# control_panel2.net
KiCad netlist of a schematic drawn in EAGLE
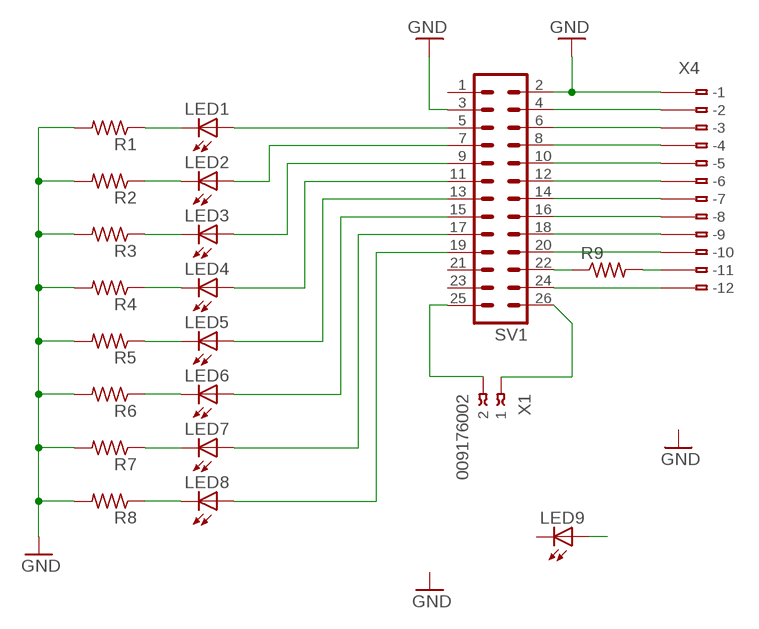
[diagram p0: schematic, sheet 1]

(export (version "E")
  (design (tool "Eeschema 10.0.6"))
  (components
    (comp (ref "LED1")
      (value "LED3MM")
      (footprint "eagle-import:LED3MM")
      (libsource (lib "eagle-import") (part "LED3MM"))
    )
    (comp (ref "LED2")
      (value "LED3MM")
      (footprint "eagle-import:LED3MM")
      (libsource (lib "eagle-import") (part "LED3MM"))
    )
    (comp (ref "LED3")
      (value "LED3MM")
      (footprint "eagle-import:LED3MM")
      (libsource (lib "eagle-import") (part "LED3MM"))
    )
    (comp (ref "LED4")
      (value "LED3MM")
      (footprint "eagle-import:LED3MM")
      (libsource (lib "eagle-import") (part "LED3MM"))
    )
    (comp (ref "LED5")
      (value "LED3MM")
      (footprint "eagle-import:LED3MM")
      (libsource (lib "eagle-import") (part "LED3MM"))
    )
    (comp (ref "LED6")
      (value "LED3MM")
      (footprint "eagle-import:LED3MM")
      (libsource (lib "eagle-import") (part "LED3MM"))
    )
    (comp (ref "LED7")
      (value "LED3MM")
      (footprint "eagle-import:LED3MM")
      (libsource (lib "eagle-import") (part "LED3MM"))
    )
    (comp (ref "LED8")
      (value "LED3MM")
      (footprint "eagle-import:LED3MM")
      (libsource (lib "eagle-import") (part "LED3MM"))
    )
    (comp (ref "LED9")
      (value "LED3MM")
      (footprint "eagle-import:LED3MM")
      (libsource (lib "eagle-import") (part "LED3MM"))
    )
    (comp (ref "R1")
      (value "R-US_0309/V")
      (footprint "eagle-import:0309V")
      (libsource (lib "eagle-import") (part "R-US_0309/V"))
    )
    (comp (ref "R2")
      (value "R-US_0309/V")
      (footprint "eagle-import:0309V")
      (libsource (lib "eagle-import") (part "R-US_0309/V"))
    )
    (comp (ref "R3")
      (value "R-US_0309/V")
      (footprint "eagle-import:0309V")
      (libsource (lib "eagle-import") (part "R-US_0309/V"))
    )
    (comp (ref "R4")
      (value "R-US_0309/V")
      (footprint "eagle-import:0309V")
      (libsource (lib "eagle-import") (part "R-US_0309/V"))
    )
    (comp (ref "R5")
      (value "R-US_0309/V")
      (footprint "eagle-import:0309V")
      (libsource (lib "eagle-import") (part "R-US_0309/V"))
    )
    (comp (ref "R6")
      (value "R-US_0309/V")
      (footprint "eagle-import:0309V")
      (libsource (lib "eagle-import") (part "R-US_0309/V"))
    )
    (comp (ref "R7")
      (value "R-US_0309/V")
      (footprint "eagle-import:0309V")
      (libsource (lib "eagle-import") (part "R-US_0309/V"))
    )
    (comp (ref "R8")
      (value "R-US_0309/V")
      (footprint "eagle-import:0309V")
      (libsource (lib "eagle-import") (part "R-US_0309/V"))
    )
    (comp (ref "R9")
      (value "R-US_0204/7")
      (footprint "eagle-import:0204_7")
      (libsource (lib "eagle-import") (part "R-US_0204/7"))
    )
    (comp (ref "SV1")
      (value "MA13-2")
      (footprint "eagle-import:MA13-2")
      (libsource (lib "eagle-import") (part "MA13-2"))
    )
    (comp (ref "X1")
      (value "009176002")
      (footprint "eagle-import:009176002")
      (fields (field (name "MPN") "009176002001006"))
      (libsource (lib "eagle-import") (part "00917?0026"))
    )
    (comp (ref "X4")
      (value "233-212")
      (footprint "eagle-import:233-212")
      (libsource (lib "eagle-import") (part "233-212"))
    )
  )
  (nets
    (net (code "1") (name "GND") (class "Default")
      (node (ref "R1") (pin "2") (pinfunction "2_2") (pintype "passive"))
      (node (ref "R2") (pin "2") (pinfunction "2_2") (pintype "passive"))
      (node (ref "R3") (pin "2") (pinfunction "2_2") (pintype "passive"))
      (node (ref "R4") (pin "2") (pinfunction "2_2") (pintype "passive"))
      (node (ref "R5") (pin "2") (pinfunction "2_2") (pintype "passive"))
      (node (ref "R6") (pin "2") (pinfunction "2_2") (pintype "passive"))
      (node (ref "R7") (pin "2") (pinfunction "2_2") (pintype "passive"))
      (node (ref "R8") (pin "2") (pinfunction "2_2") (pintype "passive"))
      (node (ref "SV1") (pin "2") (pinfunction "2_2") (pintype "passive"))
      (node (ref "SV1") (pin "3") (pinfunction "3_3") (pintype "passive"))
      (node (ref "X4") (pin "B1") (pinfunction "B-1_B1") (pintype "passive"))
    )
    (net (code "2") (name "Net-(LED1-C)") (class "Default")
      (node (ref "LED1") (pin "K") (pinfunction "C_K") (pintype "passive"))
      (node (ref "R1") (pin "1") (pinfunction "1_1") (pintype "passive"))
    )
    (net (code "3") (name "Net-(LED1-PadA)") (class "Default")
      (node (ref "LED1") (pin "A") (pinfunction "A_A") (pintype "passive"))
      (node (ref "SV1") (pin "5") (pinfunction "5_5") (pintype "passive"))
    )
    (net (code "4") (name "Net-(LED2-C)") (class "Default")
      (node (ref "LED2") (pin "K") (pinfunction "C_K") (pintype "passive"))
      (node (ref "R2") (pin "1") (pinfunction "1_1") (pintype "passive"))
    )
    (net (code "5") (name "Net-(LED2-PadA)") (class "Default")
      (node (ref "LED2") (pin "A") (pinfunction "A_A") (pintype "passive"))
      (node (ref "SV1") (pin "7") (pinfunction "7_7") (pintype "passive"))
    )
    (net (code "6") (name "Net-(LED3-C)") (class "Default")
      (node (ref "LED3") (pin "K") (pinfunction "C_K") (pintype "passive"))
      (node (ref "R3") (pin "1") (pinfunction "1_1") (pintype "passive"))
    )
    (net (code "7") (name "Net-(LED3-PadA)") (class "Default")
      (node (ref "LED3") (pin "A") (pinfunction "A_A") (pintype "passive"))
      (node (ref "SV1") (pin "9") (pinfunction "9_9") (pintype "passive"))
    )
    (net (code "8") (name "Net-(LED4-C)") (class "Default")
      (node (ref "LED4") (pin "K") (pinfunction "C_K") (pintype "passive"))
      (node (ref "R4") (pin "1") (pinfunction "1_1") (pintype "passive"))
    )
    (net (code "9") (name "Net-(LED4-PadA)") (class "Default")
      (node (ref "LED4") (pin "A") (pinfunction "A_A") (pintype "passive"))
      (node (ref "SV1") (pin "11") (pinfunction "11_11") (pintype "passive"))
    )
    (net (code "10") (name "Net-(LED5-C)") (class "Default")
      (node (ref "LED5") (pin "K") (pinfunction "C_K") (pintype "passive"))
      (node (ref "R5") (pin "1") (pinfunction "1_1") (pintype "passive"))
    )
    (net (code "11") (name "Net-(LED5-PadA)") (class "Default")
      (node (ref "LED5") (pin "A") (pinfunction "A_A") (pintype "passive"))
      (node (ref "SV1") (pin "13") (pinfunction "13_13") (pintype "passive"))
    )
    (net (code "12") (name "Net-(LED6-C)") (class "Default")
      (node (ref "LED6") (pin "K") (pinfunction "C_K") (pintype "passive"))
      (node (ref "R6") (pin "1") (pinfunction "1_1") (pintype "passive"))
    )
    (net (code "13") (name "Net-(LED6-PadA)") (class "Default")
      (node (ref "LED6") (pin "A") (pinfunction "A_A") (pintype "passive"))
      (node (ref "SV1") (pin "15") (pinfunction "15_15") (pintype "passive"))
    )
    (net (code "14") (name "Net-(LED7-C)") (class "Default")
      (node (ref "LED7") (pin "K") (pinfunction "C_K") (pintype "passive"))
      (node (ref "R7") (pin "1") (pinfunction "1_1") (pintype "passive"))
    )
    (net (code "15") (name "Net-(LED7-PadA)") (class "Default")
      (node (ref "LED7") (pin "A") (pinfunction "A_A") (pintype "passive"))
      (node (ref "SV1") (pin "17") (pinfunction "17_17") (pintype "passive"))
    )
    (net (code "16") (name "Net-(LED8-C)") (class "Default")
      (node (ref "LED8") (pin "K") (pinfunction "C_K") (pintype "passive"))
      (node (ref "R8") (pin "1") (pinfunction "1_1") (pintype "passive"))
    )
    (net (code "17") (name "Net-(LED8-PadA)") (class "Default")
      (node (ref "LED8") (pin "A") (pinfunction "A_A") (pintype "passive"))
      (node (ref "SV1") (pin "19") (pinfunction "19_19") (pintype "passive"))
    )
    (net (code "18") (name "Net-(R9-Pad1)") (class "Default")
      (node (ref "R9") (pin "1") (pinfunction "1_1") (pintype "passive"))
      (node (ref "SV1") (pin "22") (pinfunction "22_22") (pintype "passive"))
    )
    (net (code "19") (name "Net-(SV1-Pad25)") (class "Default")
      (node (ref "SV1") (pin "25") (pinfunction "25_25") (pintype "passive"))
      (node (ref "X1") (pin "2") (pinfunction "2_2") (pintype "passive"))
    )
    (net (code "20") (name "Net-(SV1-Pad26)") (class "Default")
      (node (ref "SV1") (pin "26") (pinfunction "26_26") (pintype "passive"))
      (node (ref "X1") (pin "1") (pinfunction "1_1") (pintype "passive"))
    )
    (net (code "21") (name "Net-(X4-B-2)") (class "Default")
      (node (ref "SV1") (pin "4") (pinfunction "4_4") (pintype "passive"))
      (node (ref "X4") (pin "B2") (pinfunction "B-2_B2") (pintype "passive"))
    )
    (net (code "22") (name "Net-(X4-B-3)") (class "Default")
      (node (ref "SV1") (pin "6") (pinfunction "6_6") (pintype "passive"))
      (node (ref "X4") (pin "B3") (pinfunction "B-3_B3") (pintype "passive"))
    )
    (net (code "23") (name "Net-(X4-B-4)") (class "Default")
      (node (ref "SV1") (pin "8") (pinfunction "8_8") (pintype "passive"))
      (node (ref "X4") (pin "B4") (pinfunction "B-4_B4") (pintype "passive"))
    )
    (net (code "24") (name "Net-(X4-B-5)") (class "Default")
      (node (ref "SV1") (pin "10") (pinfunction "10_10") (pintype "passive"))
      (node (ref "X4") (pin "B5") (pinfunction "B-5_B5") (pintype "passive"))
    )
    (net (code "25") (name "Net-(X4-B-6)") (class "Default")
      (node (ref "SV1") (pin "12") (pinfunction "12_12") (pintype "passive"))
      (node (ref "X4") (pin "B6") (pinfunction "B-6_B6") (pintype "passive"))
    )
    (net (code "26") (name "Net-(X4-B-7)") (class "Default")
      (node (ref "SV1") (pin "14") (pinfunction "14_14") (pintype "passive"))
      (node (ref "X4") (pin "B7") (pinfunction "B-7_B7") (pintype "passive"))
    )
    (net (code "27") (name "Net-(X4-B-8)") (class "Default")
      (node (ref "SV1") (pin "16") (pinfunction "16_16") (pintype "passive"))
      (node (ref "X4") (pin "B8") (pinfunction "B-8_B8") (pintype "passive"))
    )
    (net (code "28") (name "Net-(X4-B-9)") (class "Default")
      (node (ref "SV1") (pin "18") (pinfunction "18_18") (pintype "passive"))
      (node (ref "X4") (pin "B9") (pinfunction "B-9_B9") (pintype "passive"))
    )
    (net (code "29") (name "Net-(X4-B-10)") (class "Default")
      (node (ref "SV1") (pin "20") (pinfunction "20_20") (pintype "passive"))
      (node (ref "X4") (pin "B10") (pinfunction "B-10_B10") (pintype "passive"))
    )
    (net (code "30") (name "Net-(X4-B-11)") (class "Default")
      (node (ref "R9") (pin "2") (pinfunction "2_2") (pintype "passive"))
      (node (ref "X4") (pin "B11") (pinfunction "B-11_B11") (pintype "passive"))
    )
    (net (code "31") (name "Net-(X4-B-12)") (class "Default")
      (node (ref "SV1") (pin "24") (pinfunction "24_24") (pintype "passive"))
      (node (ref "X4") (pin "B12") (pinfunction "B-12_B12") (pintype "passive"))
    )
    (net (code "32") (name "unconnected-(LED9-C-PadK)") (class "Default")
      (node (ref "LED9") (pin "K") (pinfunction "C_K") (pintype "passive"))
    )
    (net (code "33") (name "unconnected-(LED9-PadA)") (class "Default")
      (node (ref "LED9") (pin "A") (pinfunction "A_A") (pintype "passive"))
    )
    (net (code "34") (name "unconnected-(SV1-Pad1)") (class "Default")
      (node (ref "SV1") (pin "1") (pinfunction "1_1") (pintype "passive"))
    )
    (net (code "35") (name "unconnected-(SV1-Pad21)") (class "Default")
      (node (ref "SV1") (pin "21") (pinfunction "21_21") (pintype "passive"))
    )
    (net (code "36") (name "unconnected-(SV1-Pad23)") (class "Default")
      (node (ref "SV1") (pin "23") (pinfunction "23_23") (pintype "passive"))
    )
    (net (code "37") (name "unconnected-(X4--1-PadA1)") (class "Default")
      (node (ref "X4") (pin "A1") (pinfunction "-1_A1") (pintype "passive"))
    )
    (net (code "38") (name "unconnected-(X4--2-PadA2)") (class "Default")
      (node (ref "X4") (pin "A2") (pinfunction "-2_A2") (pintype "passive"))
    )
    (net (code "39") (name "unconnected-(X4--3-PadA3)") (class "Default")
      (node (ref "X4") (pin "A3") (pinfunction "-3_A3") (pintype "passive"))
    )
    (net (code "40") (name "unconnected-(X4--4-PadA4)") (class "Default")
      (node (ref "X4") (pin "A4") (pinfunction "-4_A4") (pintype "passive"))
    )
    (net (code "41") (name "unconnected-(X4--5-PadA5)") (class "Default")
      (node (ref "X4") (pin "A5") (pinfunction "-5_A5") (pintype "passive"))
    )
    (net (code "42") (name "unconnected-(X4--6-PadA6)") (class "Default")
      (node (ref "X4") (pin "A6") (pinfunction "-6_A6") (pintype "passive"))
    )
    (net (code "43") (name "unconnected-(X4--7-PadA7)") (class "Default")
      (node (ref "X4") (pin "A7") (pinfunction "-7_A7") (pintype "passive"))
    )
    (net (code "44") (name "unconnected-(X4--8-PadA8)") (class "Default")
      (node (ref "X4") (pin "A8") (pinfunction "-8_A8") (pintype "passive"))
    )
    (net (code "45") (name "unconnected-(X4--9-PadA9)") (class "Default")
      (node (ref "X4") (pin "A9") (pinfunction "-9_A9") (pintype "passive"))
    )
    (net (code "46") (name "unconnected-(X4--10-PadA10)") (class "Default")
      (node (ref "X4") (pin "A10") (pinfunction "-10_A10") (pintype "passive"))
    )
    (net (code "47") (name "unconnected-(X4--11-PadA11)") (class "Default")
      (node (ref "X4") (pin "A11") (pinfunction "-11_A11") (pintype "passive"))
    )
    (net (code "48") (name "unconnected-(X4--12-PadA12)") (class "Default")
      (node (ref "X4") (pin "A12") (pinfunction "-12_A12") (pintype "passive"))
    )
  )
)
